# RFM96W-BB.net
KiCad netlist of a schematic drawn in EAGLE
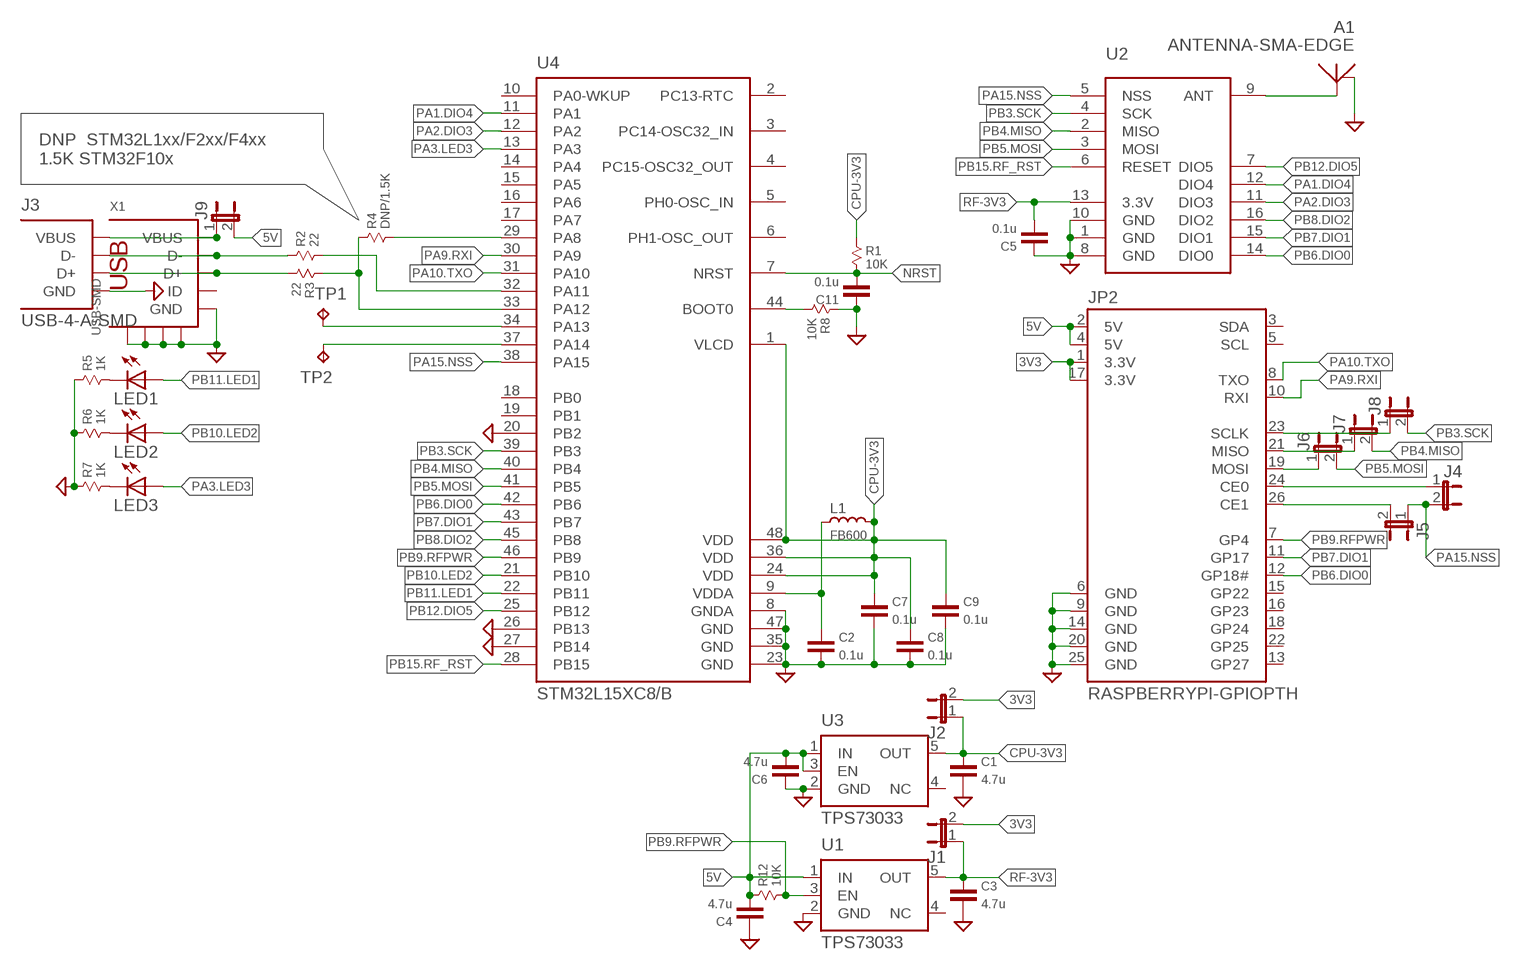
[diagram p0: schematic, sheet 1]

(export (version "E")
  (design (tool "Eeschema 10.0.6"))
  (components
    (comp (ref "A1")
      (value "ANTENNA-SMA-EDGE")
      (footprint "eagle-import:SMA-EDGE")
      (libsource (lib "eagle-import") (part "ANTENNA-SMA-EDGE"))
    )
    (comp (ref "C1")
      (value "4.7u")
      (footprint "eagle-import:0603")
      (libsource (lib "eagle-import") (part "CAP-0603"))
    )
    (comp (ref "C2")
      (value "0.1u")
      (footprint "eagle-import:0603")
      (libsource (lib "eagle-import") (part "CAP-0603"))
    )
    (comp (ref "C3")
      (value "4.7u")
      (footprint "eagle-import:0603")
      (libsource (lib "eagle-import") (part "CAP-0603"))
    )
    (comp (ref "C4")
      (value "4.7u")
      (footprint "eagle-import:0603")
      (libsource (lib "eagle-import") (part "CAP-0603"))
    )
    (comp (ref "C5")
      (value "0.1u")
      (footprint "eagle-import:0603")
      (libsource (lib "eagle-import") (part "CAP-0603"))
    )
    (comp (ref "C6")
      (value "4.7u")
      (footprint "eagle-import:0603")
      (libsource (lib "eagle-import") (part "CAP-0603"))
    )
    (comp (ref "C7")
      (value "0.1u")
      (footprint "eagle-import:0603")
      (libsource (lib "eagle-import") (part "CAP-0603"))
    )
    (comp (ref "C8")
      (value "0.1u")
      (footprint "eagle-import:0603")
      (libsource (lib "eagle-import") (part "CAP-0603"))
    )
    (comp (ref "C9")
      (value "0.1u")
      (footprint "eagle-import:0603")
      (libsource (lib "eagle-import") (part "CAP-0603"))
    )
    (comp (ref "C11")
      (value "0.1u")
      (footprint "eagle-import:0603")
      (libsource (lib "eagle-import") (part "CAP-0603"))
    )
    (comp (ref "J1")
      (value "JUMPER-2SMD-NO")
      (footprint "eagle-import:SJ_2S-NO")
      (libsource (lib "eagle-import") (part "JUMPER-2SMD-NO"))
    )
    (comp (ref "J2")
      (value "JUMPER-2SMD-NO")
      (footprint "eagle-import:SJ_2S-NO")
      (libsource (lib "eagle-import") (part "JUMPER-2SMD-NO"))
    )
    (comp (ref "J3")
      (value "USB-4-A-SMD")
      (footprint "eagle-import:USB-A-SMD")
      (libsource (lib "eagle-import") (part "USB-4-A-SMD"))
    )
    (comp (ref "J4")
      (value "JUMPER-2SMD-NO")
      (footprint "eagle-import:SJ_2S-NO")
      (libsource (lib "eagle-import") (part "JUMPER-2SMD-NO"))
    )
    (comp (ref "J5")
      (value "JUMPER-2SMD-NO")
      (footprint "eagle-import:SJ_2S-NO")
      (libsource (lib "eagle-import") (part "JUMPER-2SMD-NO"))
    )
    (comp (ref "J6")
      (value "JUMPER-2SMD-NO")
      (footprint "eagle-import:SJ_2S-NO")
      (libsource (lib "eagle-import") (part "JUMPER-2SMD-NO"))
    )
    (comp (ref "J7")
      (value "JUMPER-2SMD-NO")
      (footprint "eagle-import:SJ_2S-NO")
      (libsource (lib "eagle-import") (part "JUMPER-2SMD-NO"))
    )
    (comp (ref "J8")
      (value "JUMPER-2SMD-NO")
      (footprint "eagle-import:SJ_2S-NO")
      (libsource (lib "eagle-import") (part "JUMPER-2SMD-NO"))
    )
    (comp (ref "J9")
      (value "JUMPER-2SMD-NO")
      (footprint "eagle-import:SJ_2S-NO")
      (libsource (lib "eagle-import") (part "JUMPER-2SMD-NO"))
    )
    (comp (ref "JP2")
      (value "RASPBERRYPI-GPIOPTH")
      (footprint "eagle-import:2X13-SHROUDED")
      (libsource (lib "eagle-import") (part "RASPBERRYPI-GPIOPTH"))
    )
    (comp (ref "L1")
      (value "FB600")
      (footprint "eagle-import:0603")
      (libsource (lib "eagle-import") (part "INDUCTOR-0603"))
    )
    (comp (ref "LED1")
      (value "LEDCHIPLED_0603")
      (footprint "eagle-import:CHIPLED_0603")
      (libsource (lib "eagle-import") (part "LEDCHIPLED_0603"))
    )
    (comp (ref "LED2")
      (value "LEDCHIPLED_0603")
      (footprint "eagle-import:CHIPLED_0603")
      (libsource (lib "eagle-import") (part "LEDCHIPLED_0603"))
    )
    (comp (ref "LED3")
      (value "LEDCHIPLED_0603")
      (footprint "eagle-import:CHIPLED_0603")
      (libsource (lib "eagle-import") (part "LEDCHIPLED_0603"))
    )
    (comp (ref "R1")
      (value "10K")
      (footprint "eagle-import:0603")
      (libsource (lib "eagle-import") (part "RESISTOR-0603"))
    )
    (comp (ref "R2")
      (value "22")
      (footprint "eagle-import:0603")
      (libsource (lib "eagle-import") (part "RESISTOR-0603"))
    )
    (comp (ref "R3")
      (value "22")
      (footprint "eagle-import:0603")
      (libsource (lib "eagle-import") (part "RESISTOR-0603"))
    )
    (comp (ref "R4")
      (value "DNP/1.5K")
      (footprint "eagle-import:0603")
      (libsource (lib "eagle-import") (part "RESISTOR-0603"))
    )
    (comp (ref "R5")
      (value "1K")
      (footprint "eagle-import:0603")
      (libsource (lib "eagle-import") (part "RESISTOR-0603"))
    )
    (comp (ref "R6")
      (value "1K")
      (footprint "eagle-import:0603")
      (libsource (lib "eagle-import") (part "RESISTOR-0603"))
    )
    (comp (ref "R7")
      (value "1K")
      (footprint "eagle-import:0603")
      (libsource (lib "eagle-import") (part "RESISTOR-0603"))
    )
    (comp (ref "R8")
      (value "10K")
      (footprint "eagle-import:0603")
      (libsource (lib "eagle-import") (part "RESISTOR-0603"))
    )
    (comp (ref "R12")
      (value "10K")
      (footprint "eagle-import:0603")
      (libsource (lib "eagle-import") (part "RESISTOR-0603"))
    )
    (comp (ref "TP1")
      (value "TPTP14R")
      (footprint "eagle-import:TP14R")
      (libsource (lib "eagle-import") (part "TPTP14R"))
    )
    (comp (ref "TP2")
      (value "TPTP14R")
      (footprint "eagle-import:TP14R")
      (libsource (lib "eagle-import") (part "TPTP14R"))
    )
    (comp (ref "U1")
      (value "TPS73033")
      (footprint "eagle-import:SOT23-5")
      (libsource (lib "eagle-import") (part "TPS73033"))
    )
    (comp (ref "U2")
      (value "RFM9XW")
      (footprint "eagle-import:RFM9XW")
      (libsource (lib "eagle-import") (part "RFM9XW"))
    )
    (comp (ref "U3")
      (value "TPS73033")
      (footprint "eagle-import:SOT23-5")
      (libsource (lib "eagle-import") (part "TPS73033"))
    )
    (comp (ref "U4")
      (value "STM32L15XC8/B")
      (footprint "eagle-import:LQFP48")
      (libsource (lib "eagle-import") (part "STM32L15XC8/B"))
    )
    (comp (ref "X1")
      (value "USB-SMD")
      (footprint "eagle-import:USB-MINIB")
      (libsource (lib "eagle-import") (part "USB-SMD"))
    )
  )
  (nets
    (net (code "1") (name "3V3") (class "Default")
      (node (ref "J1") (pin "2") (pinfunction "2_2") (pintype "passive"))
      (node (ref "J2") (pin "2") (pinfunction "2_2") (pintype "passive"))
      (node (ref "JP2") (pin "1") (pinfunction "3.3V_1") (pintype "power_in"))
      (node (ref "JP2") (pin "17") (pinfunction "3.3V_17") (pintype "power_in"))
    )
    (net (code "2") (name "5V") (class "Default")
      (node (ref "C4") (pin "1") (pinfunction "1_1") (pintype "passive"))
      (node (ref "C6") (pin "1") (pinfunction "1_1") (pintype "passive"))
      (node (ref "J9") (pin "2") (pinfunction "2_2") (pintype "passive"))
      (node (ref "JP2") (pin "2") (pinfunction "5V_2") (pintype "power_in"))
      (node (ref "JP2") (pin "4") (pinfunction "5V_4") (pintype "power_in"))
      (node (ref "R12") (pin "1") (pinfunction "1_1") (pintype "passive"))
      (node (ref "U1") (pin "1") (pinfunction "IN_1") (pintype "passive"))
      (node (ref "U3") (pin "1") (pinfunction "IN_1") (pintype "passive"))
      (node (ref "U3") (pin "3") (pinfunction "EN_3") (pintype "input"))
    )
    (net (code "3") (name "CPU-3V3") (class "Default")
      (node (ref "C1") (pin "2") (pinfunction "2_2") (pintype "passive"))
      (node (ref "C7") (pin "2") (pinfunction "2_2") (pintype "passive"))
      (node (ref "C8") (pin "2") (pinfunction "2_2") (pintype "passive"))
      (node (ref "C9") (pin "2") (pinfunction "2_2") (pintype "passive"))
      (node (ref "J2") (pin "1") (pinfunction "1_1") (pintype "passive"))
      (node (ref "L1") (pin "2") (pinfunction "2_2") (pintype "passive"))
      (node (ref "R1") (pin "1") (pinfunction "1_1") (pintype "passive"))
      (node (ref "U3") (pin "5") (pinfunction "OUT_5") (pintype "passive"))
      (node (ref "U4") (pin "1") (pinfunction "VLCD_1") (pintype "passive"))
      (node (ref "U4") (pin "24") (pinfunction "VDD_24") (pintype "power_in"))
      (node (ref "U4") (pin "36") (pinfunction "VDD_36") (pintype "power_in"))
      (node (ref "U4") (pin "48") (pinfunction "VDD_48") (pintype "power_in"))
    )
    (net (code "4") (name "GND") (class "Default")
      (node (ref "A1") (pin "GND@1") (pinfunction "GND_GND@1") (pintype "power_in"))
      (node (ref "C1") (pin "1") (pinfunction "1_1") (pintype "passive"))
      (node (ref "C11") (pin "2") (pinfunction "2_2") (pintype "passive"))
      (node (ref "C2") (pin "1") (pinfunction "1_1") (pintype "passive"))
      (node (ref "C3") (pin "1") (pinfunction "1_1") (pintype "passive"))
      (node (ref "C4") (pin "2") (pinfunction "2_2") (pintype "passive"))
      (node (ref "C5") (pin "2") (pinfunction "2_2") (pintype "passive"))
      (node (ref "C6") (pin "2") (pinfunction "2_2") (pintype "passive"))
      (node (ref "C7") (pin "1") (pinfunction "1_1") (pintype "passive"))
      (node (ref "C8") (pin "1") (pinfunction "1_1") (pintype "passive"))
      (node (ref "C9") (pin "1") (pinfunction "1_1") (pintype "passive"))
      (node (ref "J3") (pin "GND") (pinfunction "GND_GND") (pintype "power_in"))
      (node (ref "JP2") (pin "14") (pinfunction "GND_14") (pintype "power_in"))
      (node (ref "JP2") (pin "20") (pinfunction "GND_20") (pintype "power_in"))
      (node (ref "JP2") (pin "25") (pinfunction "GND_25") (pintype "power_in"))
      (node (ref "JP2") (pin "6") (pinfunction "GND_6") (pintype "power_in"))
      (node (ref "JP2") (pin "9") (pinfunction "GND_9") (pintype "power_in"))
      (node (ref "R5") (pin "1") (pinfunction "1_1") (pintype "passive"))
      (node (ref "R6") (pin "1") (pinfunction "1_1") (pintype "passive"))
      (node (ref "R7") (pin "1") (pinfunction "1_1") (pintype "passive"))
      (node (ref "R8") (pin "1") (pinfunction "1_1") (pintype "passive"))
      (node (ref "U1") (pin "2") (pinfunction "GND_2") (pintype "power_in"))
      (node (ref "U2") (pin "1") (pinfunction "GND_1") (pintype "power_in"))
      (node (ref "U2") (pin "10") (pinfunction "GND_10") (pintype "power_in"))
      (node (ref "U2") (pin "8") (pinfunction "GND_8") (pintype "power_in"))
      (node (ref "U3") (pin "2") (pinfunction "GND_2") (pintype "power_in"))
      (node (ref "U4") (pin "20") (pinfunction "PB2_20") (pintype "bidirectional"))
      (node (ref "U4") (pin "23") (pinfunction "GND_23") (pintype "power_in"))
      (node (ref "U4") (pin "26") (pinfunction "PB13_26") (pintype "bidirectional"))
      (node (ref "U4") (pin "27") (pinfunction "PB14_27") (pintype "bidirectional"))
      (node (ref "U4") (pin "35") (pinfunction "GND_35") (pintype "power_in"))
      (node (ref "U4") (pin "47") (pinfunction "GND_47") (pintype "power_in"))
      (node (ref "U4") (pin "8") (pinfunction "GNDA_8") (pintype "power_in"))
      (node (ref "X1") (pin "GND") (pinfunction "GND_GND") (pintype "power_in"))
      (node (ref "X1") (pin "GND@1") (pinfunction "GND_GND@1") (pintype "power_in"))
      (node (ref "X1") (pin "GND@2") (pinfunction "GND_GND@2") (pintype "power_in"))
      (node (ref "X1") (pin "GND@3") (pinfunction "GND_GND@3") (pintype "power_in"))
      (node (ref "X1") (pin "GND@4") (pinfunction "GND_GND@4") (pintype "power_in"))
    )
    (net (code "5") (name "NRST") (class "Default")
      (node (ref "C11") (pin "1") (pinfunction "1_1") (pintype "passive"))
      (node (ref "R1") (pin "2") (pinfunction "2_2") (pintype "passive"))
      (node (ref "U4") (pin "7") (pinfunction "NRST_7") (pintype "input"))
    )
    (net (code "6") (name "Net-(J3-PadD+)") (class "Default")
      (node (ref "J3") (pin "D+") (pinfunction "D+_D+") (pintype "bidirectional"))
      (node (ref "R3") (pin "2") (pinfunction "2_2") (pintype "passive"))
      (node (ref "X1") (pin "D+") (pinfunction "D+_D+") (pintype "bidirectional"))
    )
    (net (code "7") (name "Net-(J3-PadD-)") (class "Default")
      (node (ref "J3") (pin "D-") (pinfunction "D-_D-") (pintype "bidirectional"))
      (node (ref "R2") (pin "1") (pinfunction "1_1") (pintype "passive"))
      (node (ref "X1") (pin "D-") (pinfunction "D-_D-") (pintype "bidirectional"))
    )
    (net (code "8") (name "Net-(J3-VBUS)") (class "Default")
      (node (ref "J3") (pin "VUSB") (pinfunction "VBUS_VUSB") (pintype "passive"))
      (node (ref "J9") (pin "1") (pinfunction "1_1") (pintype "passive"))
      (node (ref "X1") (pin "VBUS") (pinfunction "VBUS_VBUS") (pintype "passive"))
    )
    (net (code "9") (name "Net-(JP2-CE0)") (class "Default")
      (node (ref "J4") (pin "1") (pinfunction "1_1") (pintype "passive"))
      (node (ref "JP2") (pin "24") (pinfunction "CE0_24") (pintype "output"))
    )
    (net (code "10") (name "Net-(JP2-CE1)") (class "Default")
      (node (ref "J5") (pin "2") (pinfunction "2_2") (pintype "passive"))
      (node (ref "JP2") (pin "26") (pinfunction "CE1_26") (pintype "output"))
    )
    (net (code "11") (name "Net-(JP2-MISO)") (class "Default")
      (node (ref "J7") (pin "1") (pinfunction "1_1") (pintype "passive"))
      (node (ref "JP2") (pin "21") (pinfunction "MISO_21") (pintype "input"))
    )
    (net (code "12") (name "Net-(JP2-MOSI)") (class "Default")
      (node (ref "J6") (pin "1") (pinfunction "1_1") (pintype "passive"))
      (node (ref "JP2") (pin "19") (pinfunction "MOSI_19") (pintype "output"))
    )
    (net (code "13") (name "Net-(JP2-SCLK)") (class "Default")
      (node (ref "J8") (pin "1") (pinfunction "1_1") (pintype "passive"))
      (node (ref "JP2") (pin "23") (pinfunction "SCLK_23") (pintype "output"))
    )
    (net (code "14") (name "Net-(LED1-PadC)") (class "Default")
      (node (ref "LED1") (pin "C") (pinfunction "C_C") (pintype "passive"))
      (node (ref "R5") (pin "2") (pinfunction "2_2") (pintype "passive"))
    )
    (net (code "15") (name "Net-(LED2-PadC)") (class "Default")
      (node (ref "LED2") (pin "C") (pinfunction "C_C") (pintype "passive"))
      (node (ref "R6") (pin "2") (pinfunction "2_2") (pintype "passive"))
    )
    (net (code "16") (name "Net-(LED3-PadC)") (class "Default")
      (node (ref "LED3") (pin "C") (pinfunction "C_C") (pintype "passive"))
      (node (ref "R7") (pin "2") (pinfunction "2_2") (pintype "passive"))
    )
    (net (code "17") (name "Net-(U2-ANT)") (class "Default")
      (node (ref "A1") (pin "ANT") (pinfunction "ANT_ANT") (pintype "passive"))
      (node (ref "U2") (pin "9") (pinfunction "ANT_9") (pintype "passive"))
    )
    (net (code "18") (name "Net-(U4-BOOT0)") (class "Default")
      (node (ref "R8") (pin "2") (pinfunction "2_2") (pintype "passive"))
      (node (ref "U4") (pin "44") (pinfunction "BOOT0_44") (pintype "input"))
    )
    (net (code "19") (name "Net-(U4-PA8)") (class "Default")
      (node (ref "R4") (pin "2") (pinfunction "2_2") (pintype "passive"))
      (node (ref "U4") (pin "29") (pinfunction "PA8_29") (pintype "bidirectional"))
    )
    (net (code "20") (name "Net-(U4-PA11)") (class "Default")
      (node (ref "R2") (pin "2") (pinfunction "2_2") (pintype "passive"))
      (node (ref "U4") (pin "32") (pinfunction "PA11_32") (pintype "bidirectional"))
    )
    (net (code "21") (name "Net-(U4-PA12)") (class "Default")
      (node (ref "R3") (pin "1") (pinfunction "1_1") (pintype "passive"))
      (node (ref "R4") (pin "1") (pinfunction "1_1") (pintype "passive"))
      (node (ref "U4") (pin "33") (pinfunction "PA12_33") (pintype "bidirectional"))
    )
    (net (code "22") (name "Net-(U4-PA13)") (class "Default")
      (node (ref "TP1") (pin "TP") (pinfunction "TP_TP") (pintype "input"))
      (node (ref "U4") (pin "34") (pinfunction "PA13_34") (pintype "bidirectional"))
    )
    (net (code "23") (name "Net-(U4-PA14)") (class "Default")
      (node (ref "TP2") (pin "TP") (pinfunction "TP_TP") (pintype "input"))
      (node (ref "U4") (pin "37") (pinfunction "PA14_37") (pintype "bidirectional"))
    )
    (net (code "24") (name "Net-(U4-VDDA)") (class "Default")
      (node (ref "C2") (pin "2") (pinfunction "2_2") (pintype "passive"))
      (node (ref "L1") (pin "1") (pinfunction "1_1") (pintype "passive"))
      (node (ref "U4") (pin "9") (pinfunction "VDDA_9") (pintype "power_in"))
    )
    (net (code "25") (name "PA1.DIO4") (class "Default")
      (node (ref "U2") (pin "12") (pinfunction "DIO4_12") (pintype "bidirectional"))
      (node (ref "U4") (pin "11") (pinfunction "PA1_11") (pintype "bidirectional"))
    )
    (net (code "26") (name "PA2.DIO3") (class "Default")
      (node (ref "U2") (pin "11") (pinfunction "DIO3_11") (pintype "bidirectional"))
      (node (ref "U4") (pin "12") (pinfunction "PA2_12") (pintype "bidirectional"))
    )
    (net (code "27") (name "PA3.LED3") (class "Default")
      (node (ref "LED3") (pin "A") (pinfunction "A_A") (pintype "passive"))
      (node (ref "U4") (pin "13") (pinfunction "PA3_13") (pintype "bidirectional"))
    )
    (net (code "28") (name "PA9.RXI") (class "Default")
      (node (ref "JP2") (pin "10") (pinfunction "RXI_10") (pintype "input"))
      (node (ref "U4") (pin "30") (pinfunction "PA9_30") (pintype "bidirectional"))
    )
    (net (code "29") (name "PA10.TXO") (class "Default")
      (node (ref "JP2") (pin "8") (pinfunction "TXO_8") (pintype "output"))
      (node (ref "U4") (pin "31") (pinfunction "PA10_31") (pintype "bidirectional"))
    )
    (net (code "30") (name "PA15.NSS") (class "Default")
      (node (ref "J4") (pin "2") (pinfunction "2_2") (pintype "passive"))
      (node (ref "J5") (pin "1") (pinfunction "1_1") (pintype "passive"))
      (node (ref "U2") (pin "5") (pinfunction "NSS_5") (pintype "input"))
      (node (ref "U4") (pin "38") (pinfunction "PA15_38") (pintype "bidirectional"))
    )
    (net (code "31") (name "PB3.SCK") (class "Default")
      (node (ref "J8") (pin "2") (pinfunction "2_2") (pintype "passive"))
      (node (ref "U2") (pin "4") (pinfunction "SCK_4") (pintype "input"))
      (node (ref "U4") (pin "39") (pinfunction "PB3_39") (pintype "bidirectional"))
    )
    (net (code "32") (name "PB4.MISO") (class "Default")
      (node (ref "J7") (pin "2") (pinfunction "2_2") (pintype "passive"))
      (node (ref "U2") (pin "2") (pinfunction "MISO_2") (pintype "output"))
      (node (ref "U4") (pin "40") (pinfunction "PB4_40") (pintype "bidirectional"))
    )
    (net (code "33") (name "PB5.MOSI") (class "Default")
      (node (ref "J6") (pin "2") (pinfunction "2_2") (pintype "passive"))
      (node (ref "U2") (pin "3") (pinfunction "MOSI_3") (pintype "input"))
      (node (ref "U4") (pin "41") (pinfunction "PB5_41") (pintype "bidirectional"))
    )
    (net (code "34") (name "PB6.DIO0") (class "Default")
      (node (ref "JP2") (pin "12") (pinfunction "GP18#_12") (pintype "bidirectional"))
      (node (ref "U2") (pin "14") (pinfunction "DIO0_14") (pintype "bidirectional"))
      (node (ref "U4") (pin "42") (pinfunction "PB6_42") (pintype "bidirectional"))
    )
    (net (code "35") (name "PB7.DIO1") (class "Default")
      (node (ref "JP2") (pin "11") (pinfunction "GP17_11") (pintype "bidirectional"))
      (node (ref "U2") (pin "15") (pinfunction "DIO1_15") (pintype "bidirectional"))
      (node (ref "U4") (pin "43") (pinfunction "PB7_43") (pintype "bidirectional"))
    )
    (net (code "36") (name "PB8.DIO2") (class "Default")
      (node (ref "U2") (pin "16") (pinfunction "DIO2_16") (pintype "bidirectional"))
      (node (ref "U4") (pin "45") (pinfunction "PB8_45") (pintype "bidirectional"))
    )
    (net (code "37") (name "PB9.RFPWR") (class "Default")
      (node (ref "JP2") (pin "7") (pinfunction "GP4_7") (pintype "bidirectional"))
      (node (ref "R12") (pin "2") (pinfunction "2_2") (pintype "passive"))
      (node (ref "U1") (pin "3") (pinfunction "EN_3") (pintype "input"))
      (node (ref "U4") (pin "46") (pinfunction "PB9_46") (pintype "bidirectional"))
    )
    (net (code "38") (name "PB10.LED2") (class "Default")
      (node (ref "LED2") (pin "A") (pinfunction "A_A") (pintype "passive"))
      (node (ref "U4") (pin "21") (pinfunction "PB10_21") (pintype "bidirectional"))
    )
    (net (code "39") (name "PB11.LED1") (class "Default")
      (node (ref "LED1") (pin "A") (pinfunction "A_A") (pintype "passive"))
      (node (ref "U4") (pin "22") (pinfunction "PB11_22") (pintype "bidirectional"))
    )
    (net (code "40") (name "PB12.DIO5") (class "Default")
      (node (ref "U2") (pin "7") (pinfunction "DIO5_7") (pintype "bidirectional"))
      (node (ref "U4") (pin "25") (pinfunction "PB12_25") (pintype "bidirectional"))
    )
    (net (code "41") (name "PB15.RF_RST") (class "Default")
      (node (ref "U2") (pin "6") (pinfunction "RESET_6") (pintype "input"))
      (node (ref "U4") (pin "28") (pinfunction "PB15_28") (pintype "bidirectional"))
    )
    (net (code "42") (name "RF-3V3") (class "Default")
      (node (ref "C3") (pin "2") (pinfunction "2_2") (pintype "passive"))
      (node (ref "C5") (pin "1") (pinfunction "1_1") (pintype "passive"))
      (node (ref "J1") (pin "1") (pinfunction "1_1") (pintype "passive"))
      (node (ref "U1") (pin "5") (pinfunction "OUT_5") (pintype "passive"))
      (node (ref "U2") (pin "13") (pinfunction "3.3V_13") (pintype "power_in"))
    )
    (net (code "43") (name "unconnected-(JP2-GP22-Pad15)") (class "Default")
      (node (ref "JP2") (pin "15") (pinfunction "GP22_15") (pintype "bidirectional"))
    )
    (net (code "44") (name "unconnected-(JP2-GP23-Pad16)") (class "Default")
      (node (ref "JP2") (pin "16") (pinfunction "GP23_16") (pintype "bidirectional"))
    )
    (net (code "45") (name "unconnected-(JP2-GP24-Pad18)") (class "Default")
      (node (ref "JP2") (pin "18") (pinfunction "GP24_18") (pintype "bidirectional"))
    )
    (net (code "46") (name "unconnected-(JP2-GP25-Pad22)") (class "Default")
      (node (ref "JP2") (pin "22") (pinfunction "GP25_22") (pintype "bidirectional"))
    )
    (net (code "47") (name "unconnected-(JP2-GP27-Pad13)") (class "Default")
      (node (ref "JP2") (pin "13") (pinfunction "GP27_13") (pintype "bidirectional"))
    )
    (net (code "48") (name "unconnected-(JP2-SCL-Pad5)") (class "Default")
      (node (ref "JP2") (pin "5") (pinfunction "SCL_5") (pintype "bidirectional"))
    )
    (net (code "49") (name "unconnected-(JP2-SDA-Pad3)") (class "Default")
      (node (ref "JP2") (pin "3") (pinfunction "SDA_3") (pintype "bidirectional"))
    )
    (net (code "50") (name "unconnected-(U1-NC-Pad4)") (class "Default")
      (node (ref "U1") (pin "4") (pinfunction "NC_4") (pintype "no_connect"))
    )
    (net (code "51") (name "unconnected-(U3-NC-Pad4)") (class "Default")
      (node (ref "U3") (pin "4") (pinfunction "NC_4") (pintype "no_connect"))
    )
    (net (code "52") (name "unconnected-(U4-PA0-WKUP-Pad10)") (class "Default")
      (node (ref "U4") (pin "10") (pinfunction "PA0-WKUP_10") (pintype "bidirectional"))
    )
    (net (code "53") (name "unconnected-(U4-PA4-Pad14)") (class "Default")
      (node (ref "U4") (pin "14") (pinfunction "PA4_14") (pintype "bidirectional"))
    )
    (net (code "54") (name "unconnected-(U4-PA5-Pad15)") (class "Default")
      (node (ref "U4") (pin "15") (pinfunction "PA5_15") (pintype "bidirectional"))
    )
    (net (code "55") (name "unconnected-(U4-PA6-Pad16)") (class "Default")
      (node (ref "U4") (pin "16") (pinfunction "PA6_16") (pintype "bidirectional"))
    )
    (net (code "56") (name "unconnected-(U4-PA7-Pad17)") (class "Default")
      (node (ref "U4") (pin "17") (pinfunction "PA7_17") (pintype "bidirectional"))
    )
    (net (code "57") (name "unconnected-(U4-PB0-Pad18)") (class "Default")
      (node (ref "U4") (pin "18") (pinfunction "PB0_18") (pintype "bidirectional"))
    )
    (net (code "58") (name "unconnected-(U4-PB1-Pad19)") (class "Default")
      (node (ref "U4") (pin "19") (pinfunction "PB1_19") (pintype "bidirectional"))
    )
    (net (code "59") (name "unconnected-(U4-PC13-RTC-Pad2)") (class "Default")
      (node (ref "U4") (pin "2") (pinfunction "PC13-RTC_2") (pintype "bidirectional"))
    )
    (net (code "60") (name "unconnected-(U4-PC14-OSC32_IN-Pad3)") (class "Default")
      (node (ref "U4") (pin "3") (pinfunction "PC14-OSC32_IN_3") (pintype "bidirectional"))
    )
    (net (code "61") (name "unconnected-(U4-PC15-OSC32_OUT-Pad4)") (class "Default")
      (node (ref "U4") (pin "4") (pinfunction "PC15-OSC32_OUT_4") (pintype "bidirectional"))
    )
    (net (code "62") (name "unconnected-(U4-PH0-OSC_IN-Pad5)") (class "Default")
      (node (ref "U4") (pin "5") (pinfunction "PH0-OSC_IN_5") (pintype "bidirectional"))
    )
    (net (code "63") (name "unconnected-(U4-PH1-OSC_OUT-Pad6)") (class "Default")
      (node (ref "U4") (pin "6") (pinfunction "PH1-OSC_OUT_6") (pintype "bidirectional"))
    )
    (net (code "64") (name "unconnected-(X1-PadID)") (class "Default")
      (node (ref "X1") (pin "ID") (pinfunction "ID_ID") (pintype "bidirectional"))
    )
  )
)
